# MCISO-S07-V00-Master-PSU3V3-300mA.net
KiCad netlist of a schematic drawn in Altium Designer
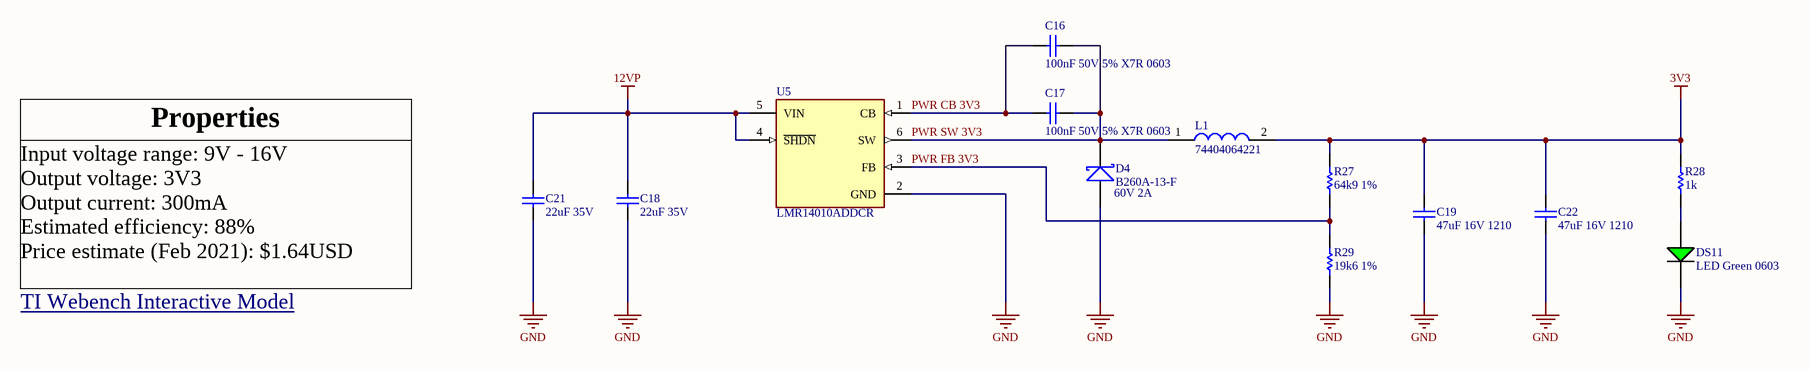
[diagram p0: MCISO-S07-V00-Master-PSU3V3-300mA.SchDoc]

(export (version "E")
  (design (tool "Eeschema 10.0.6"))
  (components
    (comp (ref "C16")
      (value "100nF 50V 5% X7R 0603")
      (footprint "Cap_Ceramic_0603")
      (description "Capacitor, Ceramic, SMD, 100nF, 50V, 5%, X7R, 0603")
      (libsource (lib "StandardCapacitors") (part "100nF 50V 5% X7R 0603"))
    )
    (comp (ref "C17")
      (value "100nF 50V 5% X7R 0603")
      (footprint "Cap_Ceramic_0603")
      (description "Capacitor, Ceramic, SMD, 100nF, 50V, 5%, X7R, 0603")
      (libsource (lib "StandardCapacitors") (part "100nF 50V 5% X7R 0603"))
    )
    (comp (ref "C18")
      (value "22uF 35V")
      (footprint "Cap_Ceramic_1206")
      (description "22µF ±20% 35V Ceramic Capacitor X5R 1206 (3216 Metric)")
      (libsource (lib "StandardCapacitors") (part "22uF 35V 20% X5R 1206"))
    )
    (comp (ref "C19")
      (value "47uF 16V 1210")
      (footprint "Cap_Ceramic_1210")
      (description "Capacitor, Ceramic, SMD, 47uF, 16V, 5%, X7R, 1210")
      (libsource (lib "StandardCapacitors") (part "47uF 16V 10% X7R 1210"))
    )
    (comp (ref "C21")
      (value "22uF 35V")
      (footprint "Cap_Ceramic_1206")
      (description "22µF ±20% 35V Ceramic Capacitor X5R 1206 (3216 Metric)")
      (libsource (lib "StandardCapacitors") (part "22uF 35V 20% X5R 1206"))
    )
    (comp (ref "C22")
      (value "47uF 16V 1210")
      (footprint "Cap_Ceramic_1210")
      (description "Capacitor, Ceramic, SMD, 47uF, 16V, 5%, X7R, 1210")
      (libsource (lib "StandardCapacitors") (part "47uF 16V 10% X7R 1210"))
    )
    (comp (ref "D4")
      (value "B260A-13-F")
      (footprint "SMA")
      (description "Diode, Schottky Barrier Rectifier, 60 V, 2 A, B260A-13-F")
      (libsource (lib "QUTMS_DiodeLibrary") (part "B260A-13-F"))
    )
    (comp (ref "DS11")
      (value "LED Green 0603")
      (footprint "LED GREEN 0603")
      (libsource (lib "QUTMS_LEDLibrary") (part "LED Green 0603"))
    )
    (comp (ref "L1")
      (value "74404064221")
      (footprint "Inductor_6x6mm")
      (description "FIXED IND 220UH 660MA 850 MOHM")
      (libsource (lib "QUTMS-MCISOLibrary") (part "74404064221"))
    )
    (comp (ref "R27")
      (value "64k9 1%")
      (footprint "Res_ThinFilm_0603")
      (description "Resistor, SMD, 64k9, 0.1W, 5%, 0603")
      (libsource (lib "StandardResistors") (part "64k9 1% 0603"))
    )
    (comp (ref "R28")
      (value "1k")
      (footprint "Res_ThinFilm_0603")
      (description "Resistor, SMD, 1k, 0.1W, 5%, 0603")
      (libsource (lib "StandardResistors") (part "1k 5% 0603"))
    )
    (comp (ref "R29")
      (value "19k6 1%")
      (footprint "Res_ThinFilm_0603")
      (description "Resistor, SMD, 19k6, 0.1W, 5%, 0603")
      (libsource (lib "StandardResistors") (part "19k6 1% 0603"))
    )
    (comp (ref "U5")
      (value "LMR14010ADDCR")
      (footprint "FP-DDC0006A-MFG")
      (description "IC REG BUCK ADJ 1A TSOT23-6")
      (fields
        (field (name "MANUFACTURER") "Texas Instruments")
        (field (name "OCTOPART") "https://octopart.com/lmr14010addcr-texas+instruments-90753290")
      )
      (libsource (lib "Altium Content Vault") (part "248534993f007311ab4e1890f26e637"))
    )
  )
  (nets
    (net (code "1") (name "/PWR CB 3V3") (class "Default")
      (node (ref "C16") (pin "1") (pinfunction "1_1") (pintype "passive"))
      (node (ref "C17") (pin "1") (pinfunction "1_1") (pintype "passive"))
      (node (ref "U5") (pin "1") (pinfunction "CB_1") (pintype "input"))
    )
    (net (code "2") (name "/PWR FB 3V3") (class "Default")
      (node (ref "R27") (pin "1") (pinfunction "1_1") (pintype "passive"))
      (node (ref "R29") (pin "2") (pinfunction "2_2") (pintype "passive"))
      (node (ref "U5") (pin "3") (pinfunction "FB_3") (pintype "input"))
    )
    (net (code "3") (name "/PWR SW 3V3") (class "Default")
      (node (ref "C16") (pin "2") (pinfunction "2_2") (pintype "passive"))
      (node (ref "C17") (pin "2") (pinfunction "2_2") (pintype "passive"))
      (node (ref "D4") (pin "K") (pinfunction "K_K") (pintype "passive"))
      (node (ref "L1") (pin "1") (pinfunction "1_1") (pintype "passive"))
      (node (ref "U5") (pin "6") (pinfunction "SW_6") (pintype "output"))
    )
    (net (code "4") (name "3V3") (class "Default")
      (node (ref "C19") (pin "2") (pinfunction "2_2") (pintype "passive"))
      (node (ref "C22") (pin "2") (pinfunction "2_2") (pintype "passive"))
      (node (ref "L1") (pin "2") (pinfunction "2_2") (pintype "passive"))
      (node (ref "R27") (pin "2") (pinfunction "2_2") (pintype "passive"))
      (node (ref "R28") (pin "2") (pinfunction "2_2") (pintype "passive"))
    )
    (net (code "5") (name "12VP") (class "Default")
      (node (ref "C18") (pin "1") (pinfunction "1_1") (pintype "passive"))
      (node (ref "C21") (pin "1") (pinfunction "1_1") (pintype "passive"))
      (node (ref "U5") (pin "4") (pinfunction "~{SHDN}_4") (pintype "input"))
      (node (ref "U5") (pin "5") (pinfunction "VIN_5") (pintype "power_in"))
    )
    (net (code "6") (name "GND") (class "Default")
      (node (ref "C18") (pin "2") (pinfunction "2_2") (pintype "passive"))
      (node (ref "C19") (pin "1") (pinfunction "1_1") (pintype "passive"))
      (node (ref "C21") (pin "2") (pinfunction "2_2") (pintype "passive"))
      (node (ref "C22") (pin "1") (pinfunction "1_1") (pintype "passive"))
      (node (ref "D4") (pin "A") (pinfunction "A_A") (pintype "passive"))
      (node (ref "DS11") (pin "2") (pinfunction "C_2") (pintype "passive"))
      (node (ref "R29") (pin "1") (pinfunction "1_1") (pintype "passive"))
      (node (ref "U5") (pin "2") (pinfunction "GND_2") (pintype "power_in"))
    )
    (net (code "7") (name "Net-(DS11-A)") (class "Default")
      (node (ref "DS11") (pin "1") (pinfunction "A_1") (pintype "passive"))
      (node (ref "R28") (pin "1") (pinfunction "1_1") (pintype "passive"))
    )
  )
)
